# CentralBoard.net
KiCad netlist of a schematic drawn in EAGLE
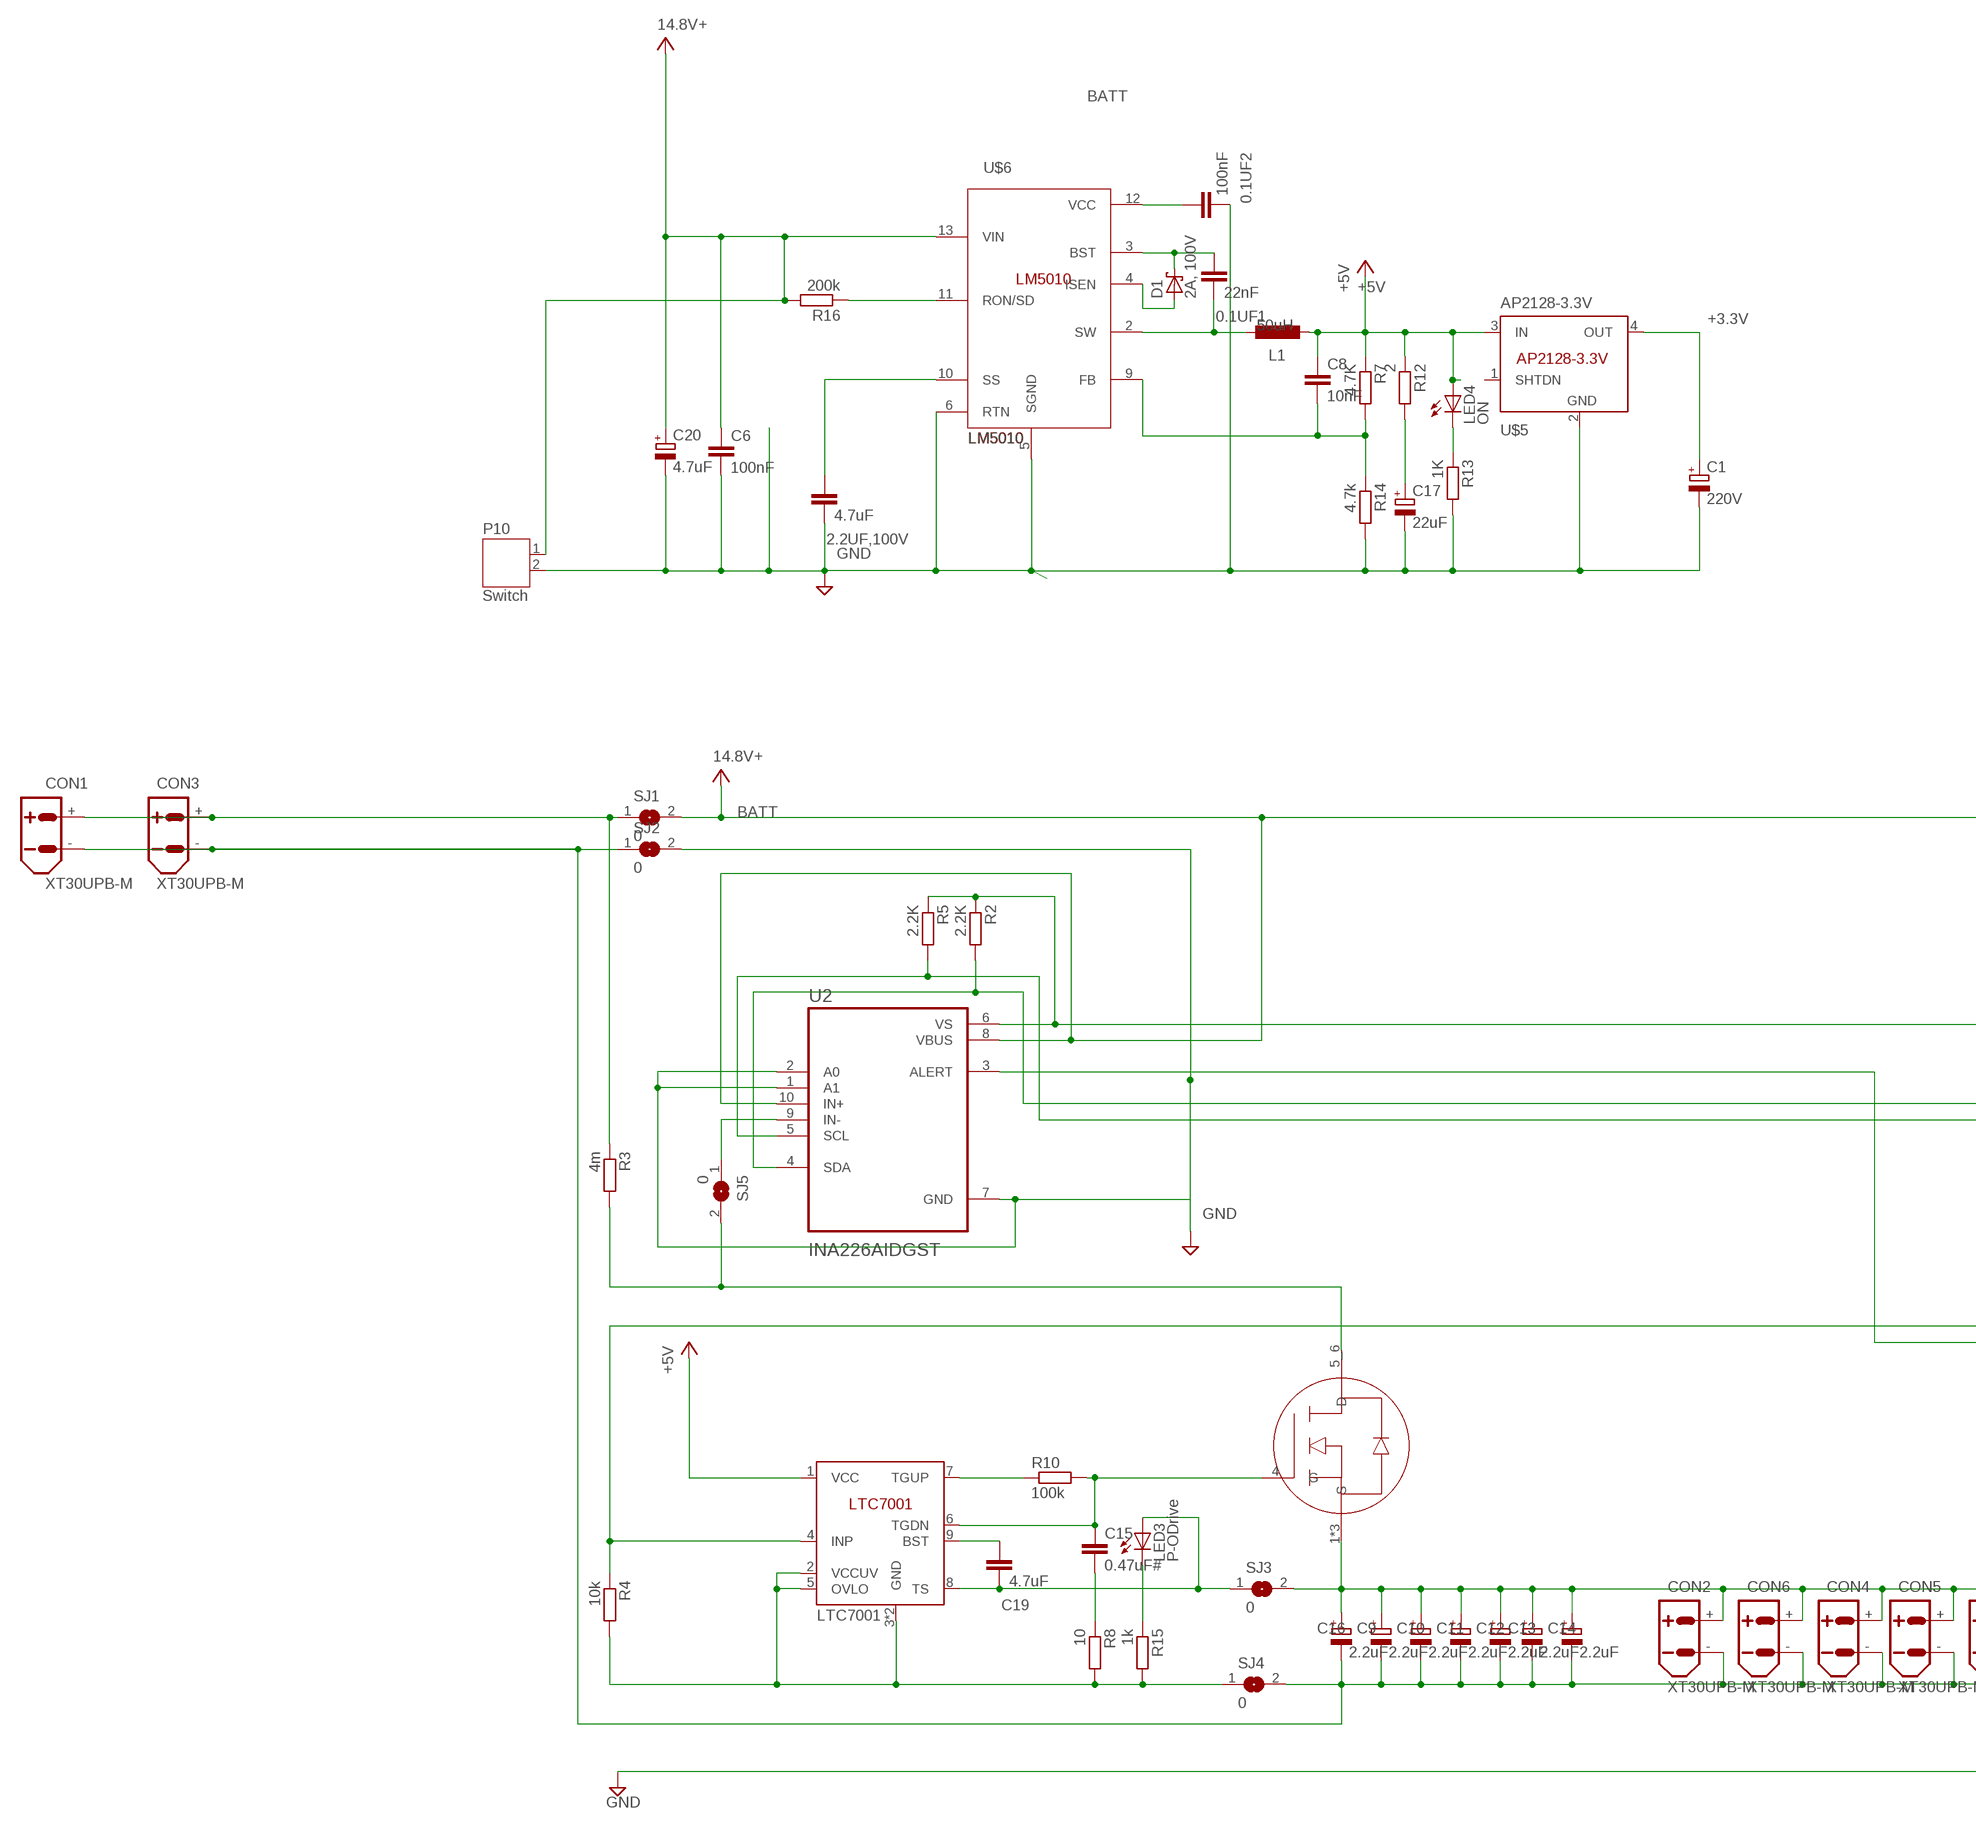
[diagram p0: schematic, sheet 1, part 1 of 2]
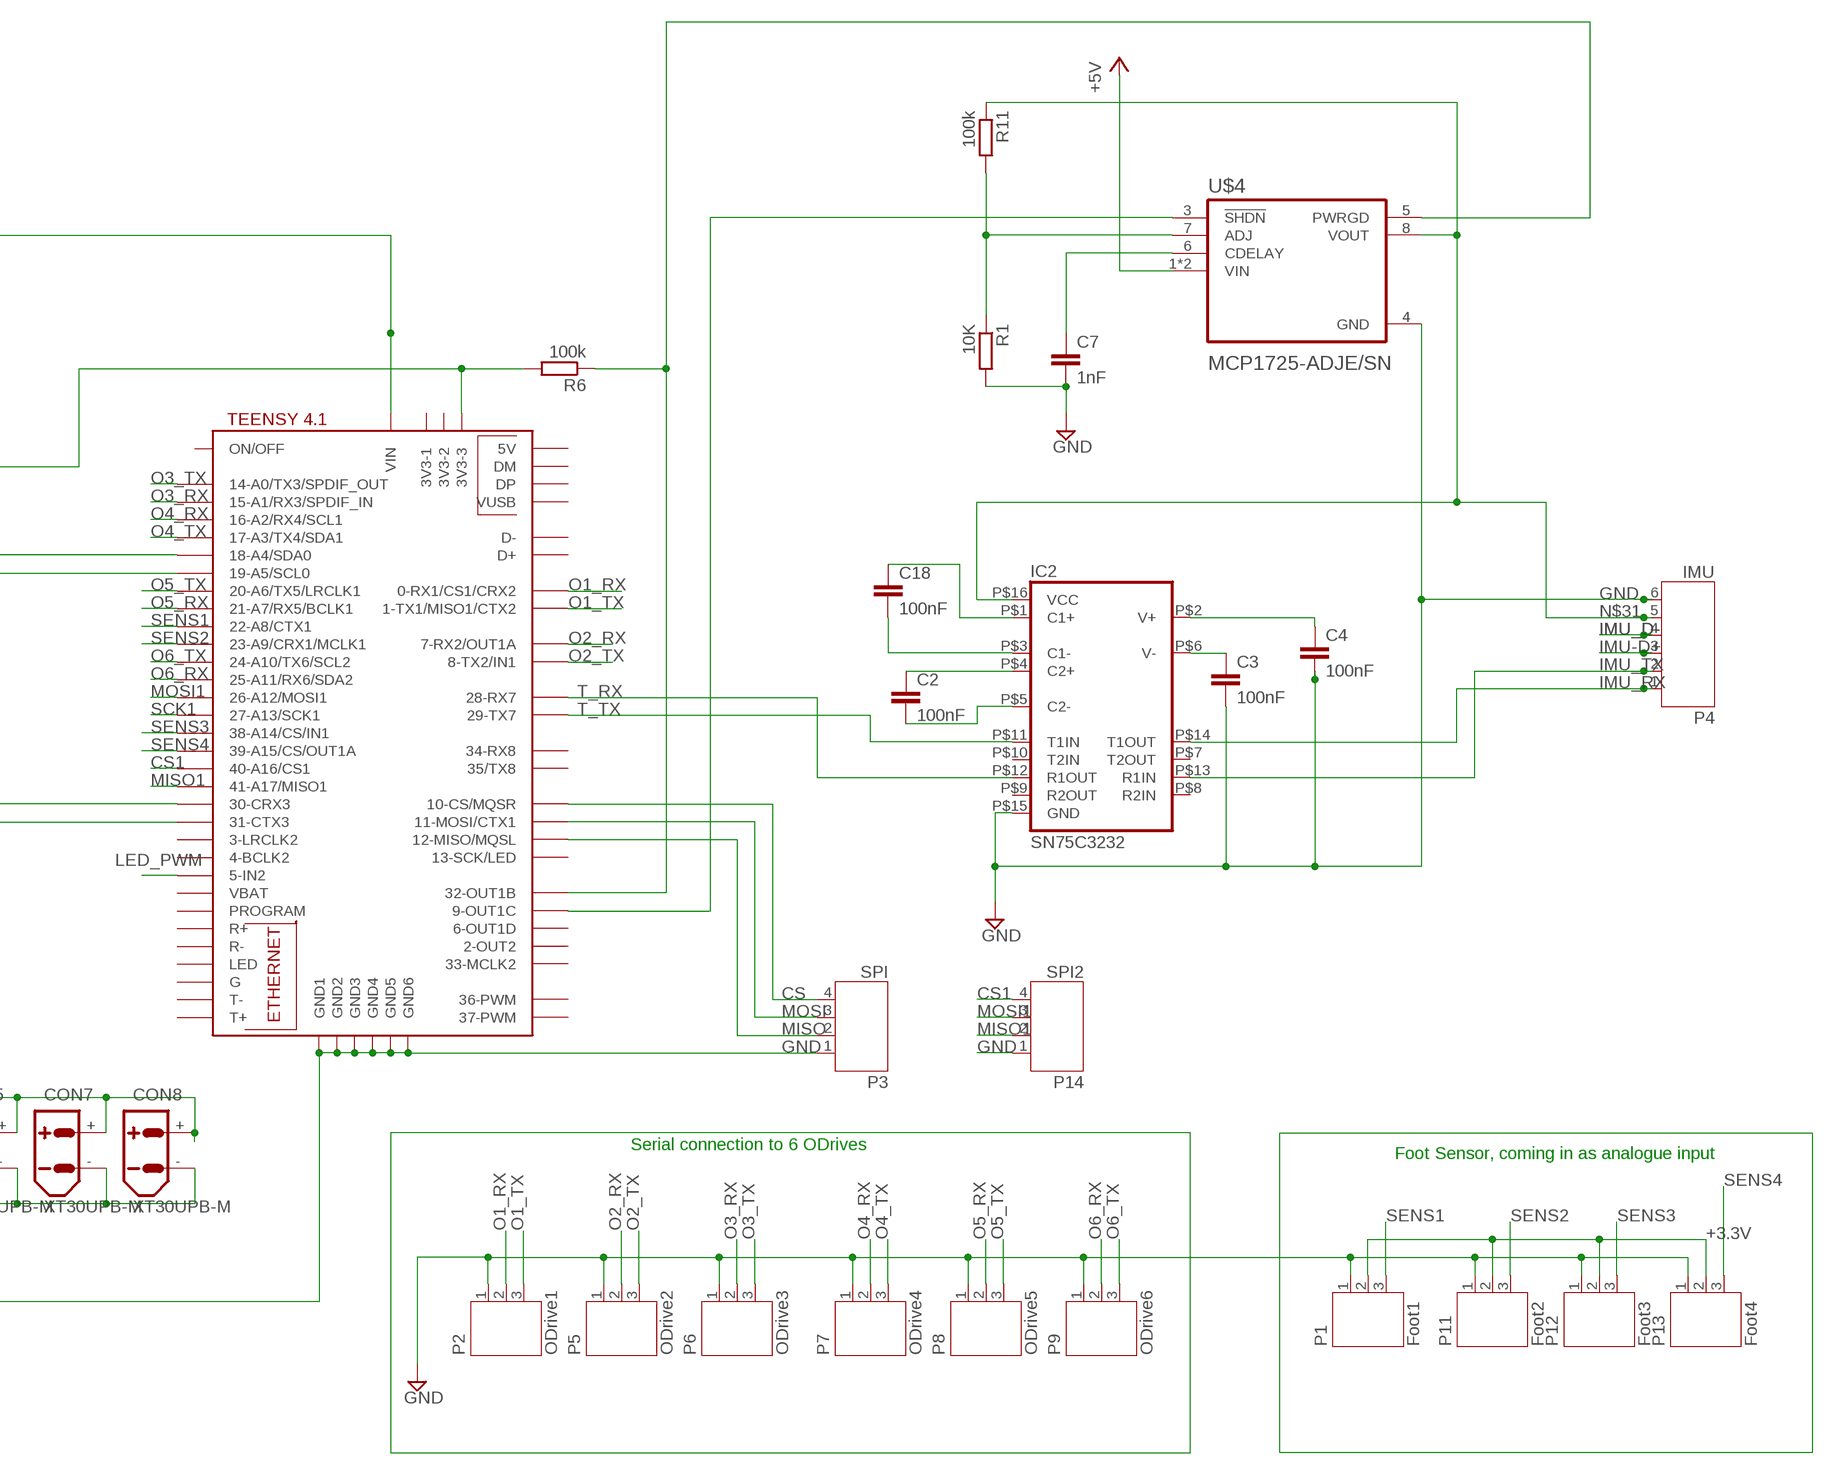
[diagram p1: schematic, sheet 1, part 2 of 2]

(export (version "E")
  (design (tool "Eeschema 10.0.6"))
  (components
    (comp (ref "0.1UF1")
      (value "22nF")
      (footprint "eagle-import:C025-025X050")
      (libsource (lib "eagle-import") (part "C-EU025-025X050"))
    )
    (comp (ref "0.1UF2")
      (value "100nF")
      (footprint "eagle-import:C025-025X050")
      (libsource (lib "eagle-import") (part "C-EU025-025X050"))
    )
    (comp (ref "2.2UF,100V")
      (value "4.7uF")
      (footprint "eagle-import:C025-025X050")
      (libsource (lib "eagle-import") (part "C-EU025-025X050"))
    )
    (comp (ref "C1")
      (value "220V")
      (footprint "eagle-import:E2,5-7")
      (libsource (lib "eagle-import") (part "CPOL-EUE2.5-7"))
    )
    (comp (ref "C2")
      (value "100nF")
      (footprint "eagle-import:C025-025X050")
      (libsource (lib "eagle-import") (part "C-EU025-025X050"))
    )
    (comp (ref "C3")
      (value "100nF")
      (footprint "eagle-import:C025-025X050")
      (libsource (lib "eagle-import") (part "C-EU025-025X050"))
    )
    (comp (ref "C4")
      (value "100nF")
      (footprint "eagle-import:C025-025X050")
      (libsource (lib "eagle-import") (part "C-EU025-025X050"))
    )
    (comp (ref "C6")
      (value "100nF")
      (footprint "eagle-import:C025-025X050")
      (libsource (lib "eagle-import") (part "C-EU025-025X050"))
    )
    (comp (ref "C7")
      (value "1nF")
      (footprint "eagle-import:C025-025X050")
      (libsource (lib "eagle-import") (part "C-EU025-025X050"))
    )
    (comp (ref "C8")
      (value "10nF")
      (footprint "eagle-import:C025-025X050")
      (libsource (lib "eagle-import") (part "C-EU025-025X050"))
    )
    (comp (ref "C9")
      (value "2.2uF")
      (footprint "eagle-import:E2-5")
      (libsource (lib "eagle-import") (part "CPOL-EUE2-5"))
    )
    (comp (ref "C10")
      (value "2.2uF")
      (footprint "eagle-import:E2-5")
      (libsource (lib "eagle-import") (part "CPOL-EUE2-5"))
    )
    (comp (ref "C11")
      (value "2.2uF")
      (footprint "eagle-import:E2-5")
      (libsource (lib "eagle-import") (part "CPOL-EUE2-5"))
    )
    (comp (ref "C12")
      (value "2.2uF")
      (footprint "eagle-import:E2-5")
      (libsource (lib "eagle-import") (part "CPOL-EUE2-5"))
    )
    (comp (ref "C13")
      (value "2.2uF")
      (footprint "eagle-import:E2-5")
      (libsource (lib "eagle-import") (part "CPOL-EUE2-5"))
    )
    (comp (ref "C14")
      (value "2.2uF")
      (footprint "eagle-import:E2-5")
      (libsource (lib "eagle-import") (part "CPOL-EUE2-5"))
    )
    (comp (ref "C15")
      (value "0.47uF#")
      (footprint "eagle-import:C025-025X050")
      (libsource (lib "eagle-import") (part "C-EU025-025X050"))
    )
    (comp (ref "C16")
      (value "2.2uF")
      (footprint "eagle-import:E2-5")
      (libsource (lib "eagle-import") (part "CPOL-EUE2-5"))
    )
    (comp (ref "C17")
      (value "22uF")
      (footprint "eagle-import:E2-4")
      (libsource (lib "eagle-import") (part "CPOL-EUE2-4"))
    )
    (comp (ref "C18")
      (value "100nF")
      (footprint "eagle-import:C025-025X050")
      (libsource (lib "eagle-import") (part "C-EU025-025X050"))
    )
    (comp (ref "C19")
      (value "4.7uF")
      (footprint "eagle-import:C025-025X050")
      (libsource (lib "eagle-import") (part "C-EU025-025X050"))
    )
    (comp (ref "C20")
      (value "4.7uF")
      (footprint "eagle-import:E2-4")
      (libsource (lib "eagle-import") (part "CPOL-EUE2-4"))
    )
    (comp (ref "CON1")
      (value "XT30UPB-M")
      (footprint "eagle-import:XT30UPB-M")
      (libsource (lib "eagle-import") (part "XT30UPB-M"))
    )
    (comp (ref "CON2")
      (value "XT30UPB-M")
      (footprint "eagle-import:XT30UPB-M")
      (libsource (lib "eagle-import") (part "XT30UPB-M"))
    )
    (comp (ref "CON3")
      (value "XT30UPB-M")
      (footprint "eagle-import:XT30UPB-M")
      (libsource (lib "eagle-import") (part "XT30UPB-M"))
    )
    (comp (ref "CON4")
      (value "XT30UPB-M")
      (footprint "eagle-import:XT30UPB-M")
      (libsource (lib "eagle-import") (part "XT30UPB-M"))
    )
    (comp (ref "CON5")
      (value "XT30UPB-M")
      (footprint "eagle-import:XT30UPB-M")
      (libsource (lib "eagle-import") (part "XT30UPB-M"))
    )
    (comp (ref "CON6")
      (value "XT30UPB-M")
      (footprint "eagle-import:XT30UPB-M")
      (libsource (lib "eagle-import") (part "XT30UPB-M"))
    )
    (comp (ref "CON7")
      (value "XT30UPB-M")
      (footprint "eagle-import:XT30UPB-M")
      (libsource (lib "eagle-import") (part "XT30UPB-M"))
    )
    (comp (ref "CON8")
      (value "XT30UPB-M")
      (footprint "eagle-import:XT30UPB-M")
      (libsource (lib "eagle-import") (part "XT30UPB-M"))
    )
    (comp (ref "D1")
      (value "2A, 100V")
      (footprint "eagle-import:DO41-10")
      (libsource (lib "eagle-import") (part "SCHOTTKY-DIODEDO41"))
    )
    (comp (ref "IC2")
      (value "SN75C3232")
      (footprint "eagle-import:SOIC16")
      (fields (field (name "MF") "Maxim Integrated") (field (name "MP") "MAX3232"))
      (libsource (lib "eagle-import") (part "MAX3232"))
    )
    (comp (ref "IC3")
      (value "LTC7001")
      (footprint "eagle-import:MSOP10")
      (fields (field (name "MPN") "AD7992BRMZ-0"))
      (libsource (lib "eagle-import") (part "LTC7001"))
    )
    (comp (ref "L1")
      (value "50uH")
      (footprint "eagle-import:0204_5")
      (libsource (lib "eagle-import") (part "L-EU0204/5"))
    )
    (comp (ref "LED3")
      (value "P-ODrive")
      (footprint "eagle-import:LED3MM")
      (libsource (lib "eagle-import") (part "LED3MM"))
    )
    (comp (ref "LED4")
      (value "ON")
      (footprint "eagle-import:LED3MM")
      (libsource (lib "eagle-import") (part "LED3MM"))
    )
    (comp (ref "P1")
      (value "Foot1")
      (footprint "eagle-import:JST-PH3")
      (libsource (lib "eagle-import") (part "JST-PH3"))
    )
    (comp (ref "P2")
      (value "ODrive1")
      (footprint "eagle-import:JST-PH3")
      (libsource (lib "eagle-import") (part "JST-PH3"))
    )
    (comp (ref "P3")
      (value "SPI")
      (footprint "eagle-import:JST-PH4")
      (libsource (lib "eagle-import") (part "JST-PH4"))
    )
    (comp (ref "P4")
      (value "IMU")
      (footprint "eagle-import:JST-PH6")
      (libsource (lib "eagle-import") (part "JST-PH6"))
    )
    (comp (ref "P5")
      (value "ODrive2")
      (footprint "eagle-import:JST-PH3")
      (libsource (lib "eagle-import") (part "JST-PH3"))
    )
    (comp (ref "P6")
      (value "ODrive3")
      (footprint "eagle-import:JST-PH3")
      (libsource (lib "eagle-import") (part "JST-PH3"))
    )
    (comp (ref "P7")
      (value "ODrive4")
      (footprint "eagle-import:JST-PH3")
      (libsource (lib "eagle-import") (part "JST-PH3"))
    )
    (comp (ref "P8")
      (value "ODrive5")
      (footprint "eagle-import:JST-PH3")
      (libsource (lib "eagle-import") (part "JST-PH3"))
    )
    (comp (ref "P9")
      (value "ODrive6")
      (footprint "eagle-import:JST-PH3")
      (libsource (lib "eagle-import") (part "JST-PH3"))
    )
    (comp (ref "P10")
      (value "Switch")
      (footprint "eagle-import:JST-PH2")
      (libsource (lib "eagle-import") (part "JST-PH2"))
    )
    (comp (ref "P11")
      (value "Foot2")
      (footprint "eagle-import:JST-PH3")
      (libsource (lib "eagle-import") (part "JST-PH3"))
    )
    (comp (ref "P12")
      (value "Foot3")
      (footprint "eagle-import:JST-PH3")
      (libsource (lib "eagle-import") (part "JST-PH3"))
    )
    (comp (ref "P13")
      (value "Foot4")
      (footprint "eagle-import:JST-PH3")
      (libsource (lib "eagle-import") (part "JST-PH3"))
    )
    (comp (ref "P14")
      (value "SPI2")
      (footprint "eagle-import:JST-PH4")
      (libsource (lib "eagle-import") (part "JST-PH4"))
    )
    (comp (ref "R1")
      (value "10K")
      (footprint "eagle-import:0204_7")
      (libsource (lib "eagle-import") (part "R-EU_0204/7"))
    )
    (comp (ref "R2")
      (value "2.2K")
      (footprint "eagle-import:0204_7")
      (libsource (lib "eagle-import") (part "R-EU_0204/7"))
    )
    (comp (ref "R3")
      (value "4m")
      (footprint "eagle-import:R2512")
      (libsource (lib "eagle-import") (part "R-EU_R2512"))
    )
    (comp (ref "R4")
      (value "10k")
      (footprint "eagle-import:0204_7")
      (libsource (lib "eagle-import") (part "R-EU_0204/7"))
    )
    (comp (ref "R5")
      (value "2.2K")
      (footprint "eagle-import:0204_7")
      (libsource (lib "eagle-import") (part "R-EU_0204/7"))
    )
    (comp (ref "R6")
      (value "100k")
      (footprint "eagle-import:0204_7")
      (libsource (lib "eagle-import") (part "R-EU_0204/7"))
    )
    (comp (ref "R7")
      (value "4.7K")
      (footprint "eagle-import:0204_7")
      (libsource (lib "eagle-import") (part "R-EU_0204/7"))
    )
    (comp (ref "R8")
      (value "10")
      (footprint "eagle-import:0204_7")
      (libsource (lib "eagle-import") (part "R-EU_0204/7"))
    )
    (comp (ref "R10")
      (value "100k")
      (footprint "eagle-import:0204_7")
      (libsource (lib "eagle-import") (part "R-EU_0204/7"))
    )
    (comp (ref "R11")
      (value "100k")
      (footprint "eagle-import:0204_7")
      (libsource (lib "eagle-import") (part "R-EU_0204/7"))
    )
    (comp (ref "R12")
      (value "2")
      (footprint "eagle-import:0204_7")
      (libsource (lib "eagle-import") (part "R-EU_0204/7"))
    )
    (comp (ref "R13")
      (value "1K")
      (footprint "eagle-import:0204_7")
      (libsource (lib "eagle-import") (part "R-EU_0204/7"))
    )
    (comp (ref "R14")
      (value "4.7k")
      (footprint "eagle-import:0204_7")
      (libsource (lib "eagle-import") (part "R-EU_0204/7"))
    )
    (comp (ref "R15")
      (value "1k")
      (footprint "eagle-import:0204_7")
      (libsource (lib "eagle-import") (part "R-EU_0204/7"))
    )
    (comp (ref "R16")
      (value "200k")
      (footprint "eagle-import:0204_7")
      (libsource (lib "eagle-import") (part "R-EU_0204/7"))
    )
    (comp (ref "SJ1") (value "0") (footprint "eagle-import:SJ") (libsource (lib "eagle-import") (part "SJ")))
    (comp (ref "SJ2") (value "0") (footprint "eagle-import:SJ") (libsource (lib "eagle-import") (part "SJ")))
    (comp (ref "SJ3") (value "0") (footprint "eagle-import:SJ") (libsource (lib "eagle-import") (part "SJ")))
    (comp (ref "SJ4") (value "0") (footprint "eagle-import:SJ") (libsource (lib "eagle-import") (part "SJ")))
    (comp (ref "SJ5") (value "0") (footprint "eagle-import:SJ") (libsource (lib "eagle-import") (part "SJ")))
    (comp (ref "U$1")
      (value "TEENSY41")
      (footprint "eagle-import:TEENSY41")
      (libsource (lib "eagle-import") (part "TEENSY41"))
    )
    (comp (ref "U$2")
      (value "DMTH8003SPS")
      (footprint "eagle-import:DIO_NTS1045EMFST1G")
      (libsource (lib "eagle-import") (part "NVMFS6H824NL-D"))
    )
    (comp (ref "U$4")
      (value "MCP1725-ADJE/SN")
      (footprint "eagle-import:SOIC127P599X175-8N")
      (fields (field (name "MF") "Microchip"))
      (libsource (lib "eagle-import") (part "MCP1725-ADJE/SN"))
    )
    (comp (ref "U$5")
      (value "AP2128-3.3V")
      (footprint "eagle-import:SOT-23-5")
      (libsource (lib "eagle-import") (part "AP2128-3.3V"))
    )
    (comp (ref "U$6")
      (value "LM5010")
      (footprint "eagle-import:TSSOP-14")
      (libsource (lib "eagle-import") (part "LM5010"))
    )
    (comp (ref "U2")
      (value "INA226AIDGST")
      (footprint "eagle-import:SOP50P490X110-10N")
      (fields (field (name "MF") "Texas Instruments"))
      (libsource (lib "eagle-import") (part "INA226AIDGST"))
    )
  )
  (nets
    (net (code "1") (name "+5V") (class "Default")
      (node (ref "C8") (pin "1") (pinfunction "1_1") (pintype "passive"))
      (node (ref "IC3") (pin "1") (pinfunction "VCC_1") (pintype "power_in"))
      (node (ref "L1") (pin "2") (pinfunction "2_2") (pintype "passive"))
      (node (ref "LED4") (pin "A") (pinfunction "A_A") (pintype "passive"))
      (node (ref "R12") (pin "1") (pinfunction "1_1") (pintype "passive"))
      (node (ref "R7") (pin "1") (pinfunction "1_1") (pintype "passive"))
      (node (ref "U$4") (pin "1") (pinfunction "VIN_1") (pintype "input"))
      (node (ref "U$4") (pin "2") (pinfunction "VIN_2") (pintype "input"))
      (node (ref "U$5") (pin "3") (pinfunction "IN_3") (pintype "input"))
    )
    (net (code "2") (name "/+3.3V") (class "Default")
      (node (ref "C1") (pin "+") (pinfunction "+_+") (pintype "passive"))
      (node (ref "P1") (pin "2") (pinfunction "2_2") (pintype "passive"))
      (node (ref "P11") (pin "2") (pinfunction "2_2") (pintype "passive"))
      (node (ref "P12") (pin "2") (pinfunction "2_2") (pintype "passive"))
      (node (ref "P13") (pin "2") (pinfunction "2_2") (pintype "passive"))
      (node (ref "U$5") (pin "4") (pinfunction "OUT_4") (pintype "output"))
    )
    (net (code "3") (name "/CS") (class "Default")
      (node (ref "P3") (pin "4") (pinfunction "4_4") (pintype "passive"))
      (node (ref "U$1") (pin "10-CS\\MQSR") (pinfunction "10-CS/MQSR_10-CS\\MQSR") (pintype "bidirectional"))
    )
    (net (code "4") (name "/CS1") (class "Default")
      (node (ref "P14") (pin "4") (pinfunction "4_4") (pintype "passive"))
      (node (ref "U$1") (pin "40-A16/CS1") (pinfunction "40-A16/CS1_40-A16/CS1") (pintype "bidirectional"))
    )
    (net (code "5") (name "/IMU-D+") (class "Default")
      (node (ref "P4") (pin "3") (pinfunction "3_3") (pintype "passive"))
    )
    (net (code "6") (name "/IMU_D-") (class "Default")
      (node (ref "P4") (pin "4") (pinfunction "4_4") (pintype "passive"))
    )
    (net (code "7") (name "/IMU_RX") (class "Default")
      (node (ref "IC2") (pin "P$14") (pinfunction "T1OUT_P$14") (pintype "output"))
      (node (ref "P4") (pin "1") (pinfunction "1_1") (pintype "passive"))
    )
    (net (code "8") (name "/IMU_TX") (class "Default")
      (node (ref "IC2") (pin "P$13") (pinfunction "R1IN_P$13") (pintype "input"))
      (node (ref "P4") (pin "2") (pinfunction "2_2") (pintype "passive"))
    )
    (net (code "9") (name "/LED_PWM") (class "Default")
      (node (ref "U$1") (pin "5-IN2") (pinfunction "5-IN2_5-IN2") (pintype "bidirectional"))
    )
    (net (code "10") (name "/MISO") (class "Default")
      (node (ref "P3") (pin "2") (pinfunction "2_2") (pintype "passive"))
      (node (ref "U$1") (pin "12-MISO/MQSL") (pinfunction "12-MISO/MQSL_12-MISO/MQSL") (pintype "bidirectional"))
    )
    (net (code "11") (name "/MISO1") (class "Default")
      (node (ref "P14") (pin "2") (pinfunction "2_2") (pintype "passive"))
      (node (ref "U$1") (pin "41-A17/MISO1") (pinfunction "41-A17/MISO1_41-A17/MISO1") (pintype "bidirectional"))
    )
    (net (code "12") (name "/MOSI") (class "Default")
      (node (ref "P3") (pin "3") (pinfunction "3_3") (pintype "passive"))
      (node (ref "U$1") (pin "11-MOSI/CTX1") (pinfunction "11-MOSI/CTX1_11-MOSI/CTX1") (pintype "bidirectional"))
    )
    (net (code "13") (name "/MOSI1") (class "Default")
      (node (ref "P14") (pin "3") (pinfunction "3_3") (pintype "passive"))
      (node (ref "U$1") (pin "26-A12/MOSI1") (pinfunction "26-A12/MOSI1_26-A12/MOSI1") (pintype "bidirectional"))
    )
    (net (code "14") (name "/N$31") (class "Default")
      (node (ref "IC2") (pin "P$16") (pinfunction "VCC_P$16") (pintype "power_in"))
      (node (ref "P4") (pin "5") (pinfunction "5_5") (pintype "passive"))
      (node (ref "R11") (pin "1") (pinfunction "1_1") (pintype "passive"))
      (node (ref "U$4") (pin "8") (pinfunction "VOUT_8") (pintype "output"))
    )
    (net (code "15") (name "/O1_RX") (class "Default")
      (node (ref "P2") (pin "2") (pinfunction "2_2") (pintype "passive"))
      (node (ref "U$1") (pin "0-RX1/CS1/CRX2") (pinfunction "0-RX1/CS1/CRX2_0-RX1/CS1/CRX2") (pintype "bidirectional"))
    )
    (net (code "16") (name "/O1_TX") (class "Default")
      (node (ref "P2") (pin "3") (pinfunction "3_3") (pintype "passive"))
      (node (ref "U$1") (pin "1-TX1/MISO1/CTX2") (pinfunction "1-TX1/MISO1/CTX2_1-TX1/MISO1/CTX2") (pintype "bidirectional"))
    )
    (net (code "17") (name "/O2_RX") (class "Default")
      (node (ref "P5") (pin "2") (pinfunction "2_2") (pintype "passive"))
      (node (ref "U$1") (pin "7-RX2/OUT1A") (pinfunction "7-RX2/OUT1A_7-RX2/OUT1A") (pintype "bidirectional"))
    )
    (net (code "18") (name "/O2_TX") (class "Default")
      (node (ref "P5") (pin "3") (pinfunction "3_3") (pintype "passive"))
      (node (ref "U$1") (pin "8-TX2/IN1") (pinfunction "8-TX2/IN1_8-TX2/IN1") (pintype "bidirectional"))
    )
    (net (code "19") (name "/O3_RX") (class "Default")
      (node (ref "P6") (pin "2") (pinfunction "2_2") (pintype "passive"))
      (node (ref "U$1") (pin "15-A1/RX3/SPDIF_IN") (pinfunction "15-A1/RX3/SPDIF_IN_15-A1/RX3/SPDIF_IN") (pintype "bidirectional"))
    )
    (net (code "20") (name "/O3_TX") (class "Default")
      (node (ref "P6") (pin "3") (pinfunction "3_3") (pintype "passive"))
      (node (ref "U$1") (pin "14-A0/TX3/SPDIF_OUT") (pinfunction "14-A0/TX3/SPDIF_OUT_14-A0/TX3/SPDIF_OUT") (pintype "bidirectional"))
    )
    (net (code "21") (name "/O4_RX") (class "Default")
      (node (ref "P7") (pin "2") (pinfunction "2_2") (pintype "passive"))
      (node (ref "U$1") (pin "16-A2/RX4/SCL1") (pinfunction "16-A2/RX4/SCL1_16-A2/RX4/SCL1") (pintype "bidirectional"))
    )
    (net (code "22") (name "/O4_TX") (class "Default")
      (node (ref "P7") (pin "3") (pinfunction "3_3") (pintype "passive"))
      (node (ref "U$1") (pin "17-A3/TX4/SDA1") (pinfunction "17-A3/TX4/SDA1_17-A3/TX4/SDA1") (pintype "bidirectional"))
    )
    (net (code "23") (name "/O5_RX") (class "Default")
      (node (ref "P8") (pin "2") (pinfunction "2_2") (pintype "passive"))
      (node (ref "U$1") (pin "21-A7/RX5/BCLK1") (pinfunction "21-A7/RX5/BCLK1_21-A7/RX5/BCLK1") (pintype "bidirectional"))
    )
    (net (code "24") (name "/O5_TX") (class "Default")
      (node (ref "P8") (pin "3") (pinfunction "3_3") (pintype "passive"))
      (node (ref "U$1") (pin "20-A6/TX5/LRCLK1") (pinfunction "20-A6/TX5/LRCLK1_20-A6/TX5/LRCLK1") (pintype "bidirectional"))
    )
    (net (code "25") (name "/O6_RX") (class "Default")
      (node (ref "P9") (pin "2") (pinfunction "2_2") (pintype "passive"))
      (node (ref "U$1") (pin "25-A11/RX6/SDA2") (pinfunction "25-A11/RX6/SDA2_25-A11/RX6/SDA2") (pintype "bidirectional"))
    )
    (net (code "26") (name "/O6_TX") (class "Default")
      (node (ref "P9") (pin "3") (pinfunction "3_3") (pintype "passive"))
      (node (ref "U$1") (pin "24-A10/TX6/SCL2") (pinfunction "24-A10/TX6/SCL2_24-A10/TX6/SCL2") (pintype "bidirectional"))
    )
    (net (code "27") (name "/SCK1") (class "Default")
      (node (ref "U$1") (pin "27-A13/SCK1") (pinfunction "27-A13/SCK1_27-A13/SCK1") (pintype "bidirectional"))
    )
    (net (code "28") (name "/SENS1") (class "Default")
      (node (ref "P1") (pin "3") (pinfunction "3_3") (pintype "passive"))
      (node (ref "U$1") (pin "22-A8/CTX1") (pinfunction "22-A8/CTX1_22-A8/CTX1") (pintype "bidirectional"))
    )
    (net (code "29") (name "/SENS2") (class "Default")
      (node (ref "P11") (pin "3") (pinfunction "3_3") (pintype "passive"))
      (node (ref "U$1") (pin "23-A9/CRX1/MCLK1") (pinfunction "23-A9/CRX1/MCLK1_23-A9/CRX1/MCLK1") (pintype "bidirectional"))
    )
    (net (code "30") (name "/SENS3") (class "Default")
      (node (ref "P12") (pin "3") (pinfunction "3_3") (pintype "passive"))
      (node (ref "U$1") (pin "38-A14/CS/IN1") (pinfunction "38-A14/CS/IN1_38-A14/CS/IN1") (pintype "bidirectional"))
    )
    (net (code "31") (name "/SENS4") (class "Default")
      (node (ref "P13") (pin "3") (pinfunction "3_3") (pintype "passive"))
      (node (ref "U$1") (pin "39-A15/CS/OUT1A") (pinfunction "39-A15/CS/OUT1A_39-A15/CS/OUT1A") (pintype "bidirectional"))
    )
    (net (code "32") (name "/T_RX") (class "Default")
      (node (ref "IC2") (pin "P$12") (pinfunction "R1OUT_P$12") (pintype "output"))
      (node (ref "U$1") (pin "28-RX7") (pinfunction "28-RX7_28-RX7") (pintype "bidirectional"))
    )
    (net (code "33") (name "/T_TX") (class "Default")
      (node (ref "IC2") (pin "P$11") (pinfunction "T1IN_P$11") (pintype "input"))
      (node (ref "U$1") (pin "29-TX7") (pinfunction "29-TX7_29-TX7") (pintype "bidirectional"))
    )
    (net (code "34") (name "14.8V+") (class "Default")
      (node (ref "C20") (pin "+") (pinfunction "+_+") (pintype "passive"))
      (node (ref "C6") (pin "1") (pinfunction "1_1") (pintype "passive"))
      (node (ref "P10") (pin "1") (pinfunction "1_1") (pintype "passive"))
      (node (ref "R16") (pin "2") (pinfunction "2_2") (pintype "passive"))
      (node (ref "SJ1") (pin "2") (pinfunction "2_2") (pintype "passive"))
      (node (ref "U$6") (pin "13") (pinfunction "VIN_13") (pintype "bidirectional"))
      (node (ref "U2") (pin "10") (pinfunction "IN+_10") (pintype "input"))
      (node (ref "U2") (pin "8") (pinfunction "VBUS_8") (pintype "power_in"))
    )
    (net (code "35") (name "GND") (class "Default")
      (node (ref "0.1UF2") (pin "2") (pinfunction "2_2") (pintype "passive"))
      (node (ref "2.2UF,100V") (pin "2") (pinfunction "2_2") (pintype "passive"))
      (node (ref "C1") (pin "-") (pinfunction "-_-") (pintype "passive"))
      (node (ref "C17") (pin "-") (pinfunction "-_-") (pintype "passive"))
      (node (ref "C20") (pin "-") (pinfunction "-_-") (pintype "passive"))
      (node (ref "C3") (pin "2") (pinfunction "2_2") (pintype "passive"))
      (node (ref "C4") (pin "2") (pinfunction "2_2") (pintype "passive"))
      (node (ref "C6") (pin "2") (pinfunction "2_2") (pintype "passive"))
      (node (ref "C7") (pin "2") (pinfunction "2_2") (pintype "passive"))
      (node (ref "IC2") (pin "P$15") (pinfunction "GND_P$15") (pintype "power_in"))
      (node (ref "P1") (pin "1") (pinfunction "1_1") (pintype "passive"))
      (node (ref "P10") (pin "2") (pinfunction "2_2") (pintype "passive"))
      (node (ref "P11") (pin "1") (pinfunction "1_1") (pintype "passive"))
      (node (ref "P12") (pin "1") (pinfunction "1_1") (pintype "passive"))
      (node (ref "P13") (pin "1") (pinfunction "1_1") (pintype "passive"))
      (node (ref "P14") (pin "1") (pinfunction "1_1") (pintype "passive"))
      (node (ref "P2") (pin "1") (pinfunction "1_1") (pintype "passive"))
      (node (ref "P3") (pin "1") (pinfunction "1_1") (pintype "passive"))
      (node (ref "P4") (pin "6") (pinfunction "6_6") (pintype "passive"))
      (node (ref "P5") (pin "1") (pinfunction "1_1") (pintype "passive"))
      (node (ref "P6") (pin "1") (pinfunction "1_1") (pintype "passive"))
      (node (ref "P7") (pin "1") (pinfunction "1_1") (pintype "passive"))
      (node (ref "P8") (pin "1") (pinfunction "1_1") (pintype "passive"))
      (node (ref "P9") (pin "1") (pinfunction "1_1") (pintype "passive"))
      (node (ref "R1") (pin "2") (pinfunction "2_2") (pintype "passive"))
      (node (ref "R13") (pin "2") (pinfunction "2_2") (pintype "passive"))
      (node (ref "R14") (pin "2") (pinfunction "2_2") (pintype "passive"))
      (node (ref "SJ2") (pin "2") (pinfunction "2_2") (pintype "passive"))
      (node (ref "U$1") (pin "GND1") (pinfunction "GND1_GND1") (pintype "bidirectional"))
      (node (ref "U$1") (pin "GND2") (pinfunction "GND2_GND2") (pintype "bidirectional"))
      (node (ref "U$1") (pin "GND3") (pinfunction "GND3_GND3") (pintype "bidirectional"))
      (node (ref "U$1") (pin "GND4") (pinfunction "GND4_GND4") (pintype "bidirectional"))
      (node (ref "U$1") (pin "GND5") (pinfunction "GND5_GND5") (pintype "bidirectional"))
      (node (ref "U$1") (pin "GND6") (pinfunction "GND6_GND6") (pintype "bidirectional"))
      (node (ref "U$4") (pin "4") (pinfunction "GND_4") (pintype "power_in"))
      (node (ref "U$5") (pin "2") (pinfunction "GND_2") (pintype "power_in"))
      (node (ref "U$6") (pin "5") (pinfunction "SGND_5") (pintype "bidirectional"))
      (node (ref "U$6") (pin "6") (pinfunction "RTN_6") (pintype "bidirectional"))
      (node (ref "U2") (pin "1") (pinfunction "A1_1") (pintype "input"))
      (node (ref "U2") (pin "2") (pinfunction "A0_2") (pintype "input"))
      (node (ref "U2") (pin "7") (pinfunction "GND_7") (pintype "power_in"))
    )
    (net (code "36") (name "Net-(C10-Pad+)") (class "Default")
      (node (ref "C10") (pin "+") (pinfunction "+_+") (pintype "passive"))
      (node (ref "C11") (pin "+") (pinfunction "+_+") (pintype "passive"))
      (node (ref "C12") (pin "+") (pinfunction "+_+") (pintype "passive"))
      (node (ref "C13") (pin "+") (pinfunction "+_+") (pintype "passive"))
      (node (ref "C14") (pin "+") (pinfunction "+_+") (pintype "passive"))
      (node (ref "C16") (pin "+") (pinfunction "+_+") (pintype "passive"))
      (node (ref "C9") (pin "+") (pinfunction "+_+") (pintype "passive"))
      (node (ref "CON2") (pin "+") (pinfunction "+_+") (pintype "power_in"))
      (node (ref "CON4") (pin "+") (pinfunction "+_+") (pintype "power_in"))
      (node (ref "CON5") (pin "+") (pinfunction "+_+") (pintype "power_in"))
      (node (ref "CON6") (pin "+") (pinfunction "+_+") (pintype "power_in"))
      (node (ref "CON7") (pin "+") (pinfunction "+_+") (pintype "power_in"))
      (node (ref "CON8") (pin "+") (pinfunction "+_+") (pintype "power_in"))
      (node (ref "SJ3") (pin "2") (pinfunction "2_2") (pintype "passive"))
      (node (ref "U$2") (pin "1") (pinfunction "S_1") (pintype "bidirectional"))
      (node (ref "U$2") (pin "2") (pinfunction "S_2") (pintype "bidirectional"))
      (node (ref "U$2") (pin "3") (pinfunction "S_3") (pintype "bidirectional"))
    )
    (net (code "37") (name "Net-(C10-Pad-)") (class "Default")
      (node (ref "C10") (pin "-") (pinfunction "-_-") (pintype "passive"))
      (node (ref "C11") (pin "-") (pinfunction "-_-") (pintype "passive"))
      (node (ref "C12") (pin "-") (pinfunction "-_-") (pintype "passive"))
      (node (ref "C13") (pin "-") (pinfunction "-_-") (pintype "passive"))
      (node (ref "C14") (pin "-") (pinfunction "-_-") (pintype "passive"))
      (node (ref "C16") (pin "-") (pinfunction "-_-") (pintype "passive"))
      (node (ref "C9") (pin "-") (pinfunction "-_-") (pintype "passive"))
      (node (ref "CON1") (pin "-") (pinfunction "-_-") (pintype "power_in"))
      (node (ref "CON2") (pin "-") (pinfunction "-_-") (pintype "power_in"))
      (node (ref "CON3") (pin "-") (pinfunction "-_-") (pintype "power_in"))
      (node (ref "CON4") (pin "-") (pinfunction "-_-") (pintype "power_in"))
      (node (ref "CON5") (pin "-") (pinfunction "-_-") (pintype "power_in"))
      (node (ref "CON6") (pin "-") (pinfunction "-_-") (pintype "power_in"))
      (node (ref "CON7") (pin "-") (pinfunction "-_-") (pintype "power_in"))
      (node (ref "CON8") (pin "-") (pinfunction "-_-") (pintype "power_in"))
      (node (ref "SJ2") (pin "1") (pinfunction "1_1") (pintype "passive"))
      (node (ref "SJ4") (pin "2") (pinfunction "2_2") (pintype "passive"))
    )
    (net (code "38") (name "Net-(C15-Pad2)") (class "Default")
      (node (ref "C15") (pin "2") (pinfunction "2_2") (pintype "passive"))
      (node (ref "R8") (pin "1") (pinfunction "1_1") (pintype "passive"))
    )
    (net (code "39") (name "Net-(C17-Pad+)") (class "Default")
      (node (ref "C17") (pin "+") (pinfunction "+_+") (pintype "passive"))
      (node (ref "R12") (pin "2") (pinfunction "2_2") (pintype "passive"))
    )
    (net (code "40") (name "Net-(CON1-Pad+)") (class "Default")
      (node (ref "CON1") (pin "+") (pinfunction "+_+") (pintype "power_in"))
      (node (ref "CON3") (pin "+") (pinfunction "+_+") (pintype "power_in"))
      (node (ref "R3") (pin "1") (pinfunction "1_1") (pintype "passive"))
      (node (ref "SJ1") (pin "1") (pinfunction "1_1") (pintype "passive"))
    )
    (net (code "41") (name "Net-(IC2-C1+)") (class "Default")
      (node (ref "C18") (pin "1") (pinfunction "1_1") (pintype "passive"))
      (node (ref "IC2") (pin "P$1") (pinfunction "C1+_P$1") (pintype "passive"))
    )
    (net (code "42") (name "Net-(IC2-C1-)") (class "Default")
      (node (ref "C18") (pin "2") (pinfunction "2_2") (pintype "passive"))
      (node (ref "IC2") (pin "P$3") (pinfunction "C1-_P$3") (pintype "passive"))
    )
    (net (code "43") (name "Net-(IC2-C2+)") (class "Default")
      (node (ref "C2") (pin "1") (pinfunction "1_1") (pintype "passive"))
      (node (ref "IC2") (pin "P$4") (pinfunction "C2+_P$4") (pintype "passive"))
    )
    (net (code "44") (name "Net-(IC2-C2-)") (class "Default")
      (node (ref "C2") (pin "2") (pinfunction "2_2") (pintype "passive"))
      (node (ref "IC2") (pin "P$5") (pinfunction "C2-_P$5") (pintype "passive"))
    )
    (net (code "45") (name "Net-(IC2-V+)") (class "Default")
      (node (ref "C4") (pin "1") (pinfunction "1_1") (pintype "passive"))
      (node (ref "IC2") (pin "P$2") (pinfunction "V+_P$2") (pintype "passive"))
    )
    (net (code "46") (name "Net-(IC2-V-)") (class "Default")
      (node (ref "C3") (pin "1") (pinfunction "1_1") (pintype "passive"))
      (node (ref "IC2") (pin "P$6") (pinfunction "V-_P$6") (pintype "passive"))
    )
    (net (code "47") (name "Net-(IC3-BST)") (class "Default")
      (node (ref "C19") (pin "1") (pinfunction "1_1") (pintype "passive"))
      (node (ref "IC3") (pin "9") (pinfunction "BST_9") (pintype "input"))
    )
    (net (code "48") (name "Net-(IC3-INP)") (class "Default")
      (node (ref "IC3") (pin "4") (pinfunction "INP_4") (pintype "input"))
      (node (ref "R4") (pin "1") (pinfunction "1_1") (pintype "passive"))
      (node (ref "U$1") (pin "30-CRX3") (pinfunction "30-CRX3_30-CRX3") (pintype "bidirectional"))
    )
    (net (code "49") (name "Net-(IC3-OVLO)") (class "Default")
      (node (ref "IC3") (pin "11") (pinfunction "GND_11") (pintype "power_in"))
      (node (ref "IC3") (pin "2") (pinfunction "VCCUV_2") (pintype "input"))
      (node (ref "IC3") (pin "3") (pinfunction "GND_3") (pintype "power_in"))
      (node (ref "IC3") (pin "5") (pinfunction "OVLO_5") (pintype "power_in"))
      (node (ref "R15") (pin "2") (pinfunction "2_2") (pintype "passive"))
      (node (ref "R4") (pin "2") (pinfunction "2_2") (pintype "passive"))
      (node (ref "R8") (pin "2") (pinfunction "2_2") (pintype "passive"))
      (node (ref "SJ4") (pin "1") (pinfunction "1_1") (pintype "passive"))
    )
    (net (code "50") (name "Net-(IC3-TGDN)") (class "Default")
      (node (ref "C15") (pin "1") (pinfunction "1_1") (pintype "passive"))
      (node (ref "IC3") (pin "6") (pinfunction "TGDN_6") (pintype "output"))
      (node (ref "R10") (pin "2") (pinfunction "2_2") (pintype "passive"))
      (node (ref "U$2") (pin "4") (pinfunction "G_4") (pintype "bidirectional"))
    )
    (net (code "51") (name "Net-(IC3-TGUP)") (class "Default")
      (node (ref "IC3") (pin "7") (pinfunction "TGUP_7") (pintype "input"))
      (node (ref "R10") (pin "1") (pinfunction "1_1") (pintype "passive"))
    )
    (net (code "52") (name "Net-(IC3-TS)") (class "Default")
      (node (ref "C19") (pin "2") (pinfunction "2_2") (pintype "passive"))
      (node (ref "IC3") (pin "8") (pinfunction "TS_8") (pintype "bidirectional"))
      (node (ref "LED3") (pin "A") (pinfunction "A_A") (pintype "passive"))
      (node (ref "SJ3") (pin "1") (pinfunction "1_1") (pintype "passive"))
    )
    (net (code "53") (name "Net-(LED3-C)") (class "Default")
      (node (ref "LED3") (pin "K") (pinfunction "C_K") (pintype "passive"))
      (node (ref "R15") (pin "1") (pinfunction "1_1") (pintype "passive"))
    )
    (net (code "54") (name "Net-(LED4-C)") (class "Default")
      (node (ref "LED4") (pin "K") (pinfunction "C_K") (pintype "passive"))
      (node (ref "R13") (pin "1") (pinfunction "1_1") (pintype "passive"))
    )
    (net (code "55") (name "Net-(U$2-D)") (class "Default")
      (node (ref "R3") (pin "2") (pinfunction "2_2") (pintype "passive"))
      (node (ref "SJ5") (pin "2") (pinfunction "2_2") (pintype "passive"))
      (node (ref "U$2") (pin "5_6") (pinfunction "D_5_6") (pintype "bidirectional"))
    )
    (net (code "56") (name "Net-(U$4-ADJ)") (class "Default")
      (node (ref "R1") (pin "1") (pinfunction "1_1") (pintype "passive"))
      (node (ref "R11") (pin "2") (pinfunction "2_2") (pintype "passive"))
      (node (ref "U$4") (pin "7") (pinfunction "ADJ_7") (pintype "input"))
    )
    (net (code "57") (name "Net-(U$4-CDELAY)") (class "Default")
      (node (ref "C7") (pin "1") (pinfunction "1_1") (pintype "passive"))
      (node (ref "U$4") (pin "6") (pinfunction "CDELAY_6") (pintype "input"))
    )
    (net (code "58") (name "Net-(U$4-PWRGD)") (class "Default")
      (node (ref "R6") (pin "1") (pinfunction "1_1") (pintype "passive"))
      (node (ref "U$1") (pin "32-OUT1B") (pinfunction "32-OUT1B_32-OUT1B") (pintype "bidirectional"))
      (node (ref "U$4") (pin "5") (pinfunction "PWRGD_5") (pintype "output"))
    )
    (net (code "59") (name "Net-(U$4-~{SHDN})") (class "Default")
      (node (ref "U$1") (pin "9-OUT1C") (pinfunction "9-OUT1C_9-OUT1C") (pintype "bidirectional"))
      (node (ref "U$4") (pin "3") (pinfunction "~{SHDN}_3") (pintype "input"))
    )
    (net (code "60") (name "Net-(U$6-BST)") (class "Default")
      (node (ref "0.1UF1") (pin "1") (pinfunction "1_1") (pintype "passive"))
      (node (ref "D1") (pin "C") (pinfunction "C_C") (pintype "passive"))
      (node (ref "U$6") (pin "3") (pinfunction "BST_3") (pintype "bidirectional"))
    )
    (net (code "61") (name "Net-(U$6-FB)") (class "Default")
      (node (ref "C8") (pin "2") (pinfunction "2_2") (pintype "passive"))
      (node (ref "R14") (pin "1") (pinfunction "1_1") (pintype "passive"))
      (node (ref "R7") (pin "2") (pinfunction "2_2") (pintype "passive"))
      (node (ref "U$6") (pin "9") (pinfunction "FB_9") (pintype "bidirectional"))
    )
    (net (code "62") (name "Net-(U$6-ISEN)") (class "Default")
      (node (ref "D1") (pin "A") (pinfunction "A_A") (pintype "passive"))
      (node (ref "U$6") (pin "4") (pinfunction "ISEN_4") (pintype "bidirectional"))
    )
    (net (code "63") (name "Net-(U$6-RON{slash}SD)") (class "Default")
      (node (ref "R16") (pin "1") (pinfunction "1_1") (pintype "passive"))
      (node (ref "U$6") (pin "11") (pinfunction "RON/SD_11") (pintype "bidirectional"))
    )
    (net (code "64") (name "Net-(U$6-SS)") (class "Default")
      (node (ref "2.2UF,100V") (pin "1") (pinfunction "1_1") (pintype "passive"))
      (node (ref "U$6") (pin "10") (pinfunction "SS_10") (pintype "bidirectional"))
    )
    (net (code "65") (name "Net-(U$6-SW)") (class "Default")
      (node (ref "0.1UF1") (pin "2") (pinfunction "2_2") (pintype "passive"))
      (node (ref "L1") (pin "1") (pinfunction "1_1") (pintype "passive"))
      (node (ref "U$6") (pin "2") (pinfunction "SW_2") (pintype "bidirectional"))
    )
    (net (code "66") (name "Net-(U$6-VCC)") (class "Default")
      (node (ref "0.1UF2") (pin "1") (pinfunction "1_1") (pintype "passive"))
      (node (ref "U$6") (pin "12") (pinfunction "VCC_12") (pintype "bidirectional"))
    )
    (net (code "67") (name "Net-(U2-ALERT)") (class "Default")
      (node (ref "U$1") (pin "31-CTX3") (pinfunction "31-CTX3_31-CTX3") (pintype "bidirectional"))
      (node (ref "U2") (pin "3") (pinfunction "ALERT_3") (pintype "output"))
    )
    (net (code "68") (name "Net-(U2-IN-)") (class "Default")
      (node (ref "SJ5") (pin "1") (pinfunction "1_1") (pintype "passive"))
      (node (ref "U2") (pin "9") (pinfunction "IN-_9") (pintype "input"))
    )
    (net (code "69") (name "Net-(U2-SCL)") (class "Default")
      (node (ref "R5") (pin "2") (pinfunction "2_2") (pintype "passive"))
      (node (ref "U$1") (pin "19-A5/SCL0") (pinfunction "19-A5/SCL0_19-A5/SCL0") (pintype "bidirectional"))
      (node (ref "U2") (pin "5") (pinfunction "SCL_5") (pintype "input"))
    )
    (net (code "70") (name "Net-(U2-SDA)") (class "Default")
      (node (ref "R2") (pin "2") (pinfunction "2_2") (pintype "passive"))
      (node (ref "U$1") (pin "18-A4/SDA0") (pinfunction "18-A4/SDA0_18-A4/SDA0") (pintype "bidirectional"))
      (node (ref "U2") (pin "4") (pinfunction "SDA_4") (pintype "bidirectional"))
    )
    (net (code "71") (name "Net-(U2-VS)") (class "Default")
      (node (ref "R2") (pin "1") (pinfunction "1_1") (pintype "passive"))
      (node (ref "R5") (pin "1") (pinfunction "1_1") (pintype "passive"))
      (node (ref "R6") (pin "2") (pinfunction "2_2") (pintype "passive"))
      (node (ref "U$1") (pin "3V3-3") (pinfunction "3V3-3_3V3-3") (pintype "bidirectional"))
      (node (ref "U2") (pin "6") (pinfunction "VS_6") (pintype "power_in"))
    )
    (net (code "72") (name "unconnected-(IC2-R2IN-PadP$8)") (class "Default")
      (node (ref "IC2") (pin "P$8") (pinfunction "R2IN_P$8") (pintype "input"))
    )
    (net (code "73") (name "unconnected-(IC2-R2OUT-PadP$9)") (class "Default")
      (node (ref "IC2") (pin "P$9") (pinfunction "R2OUT_P$9") (pintype "output"))
    )
    (net (code "74") (name "unconnected-(IC2-T2IN-PadP$10)") (class "Default")
      (node (ref "IC2") (pin "P$10") (pinfunction "T2IN_P$10") (pintype "input"))
    )
    (net (code "75") (name "unconnected-(IC2-T2OUT-PadP$7)") (class "Default")
      (node (ref "IC2") (pin "P$7") (pinfunction "T2OUT_P$7") (pintype "output"))
    )
    (net (code "76") (name "unconnected-(U$1-5V-Pad+5V)") (class "Default")
      (node (ref "U$1") (pin "+5V") (pinfunction "5V_+5V") (pintype "bidirectional"))
    )
    (net (code "77") (name "unconnected-(U$1-35{slash}TX8-Pad35-TX8)") (class "Default")
      (node (ref "U$1") (pin "35-TX8") (pinfunction "35/TX8_35-TX8") (pintype "bidirectional"))
    )
    (net (code "78") (name "unconnected-(U$1-Pad2-OUT2)") (class "Default")
      (node (ref "U$1") (pin "2-OUT2") (pinfunction "2-OUT2_2-OUT2") (pintype "bidirectional"))
    )
    (net (code "79") (name "unconnected-(U$1-Pad3-LRCLK2)") (class "Default")
      (node (ref "U$1") (pin "3-LRCLK2") (pinfunction "3-LRCLK2_3-LRCLK2") (pintype "bidirectional"))
    )
    (net (code "80") (name "unconnected-(U$1-Pad3V3-1)") (class "Default")
      (node (ref "U$1") (pin "3V3-1") (pinfunction "3V3-1_3V3-1") (pintype "bidirectional"))
    )
    (net (code "81") (name "unconnected-(U$1-Pad3V3-2)") (class "Default")
      (node (ref "U$1") (pin "3V3-2") (pinfunction "3V3-2_3V3-2") (pintype "bidirectional"))
    )
    (net (code "82") (name "unconnected-(U$1-Pad4-BCLK2)") (class "Default")
      (node (ref "U$1") (pin "4-BCLK2") (pinfunction "4-BCLK2_4-BCLK2") (pintype "bidirectional"))
    )
    (net (code "83") (name "unconnected-(U$1-Pad6-OUT1D)") (class "Default")
      (node (ref "U$1") (pin "6-OUT1D") (pinfunction "6-OUT1D_6-OUT1D") (pintype "bidirectional"))
    )
    (net (code "84") (name "unconnected-(U$1-Pad13-SCK{slash}LED)") (class "Default")
      (node (ref "U$1") (pin "13-SCK/LED") (pinfunction "13-SCK/LED_13-SCK/LED") (pintype "bidirectional"))
    )
    (net (code "85") (name "unconnected-(U$1-Pad33-MCLK2)") (class "Default")
      (node (ref "U$1") (pin "33-MCLK2") (pinfunction "33-MCLK2_33-MCLK2") (pintype "bidirectional"))
    )
    (net (code "86") (name "unconnected-(U$1-Pad34-RX8)") (class "Default")
      (node (ref "U$1") (pin "34-RX8") (pinfunction "34-RX8_34-RX8") (pintype "bidirectional"))
    )
    (net (code "87") (name "unconnected-(U$1-Pad36-PWM)") (class "Default")
      (node (ref "U$1") (pin "36-PWM") (pinfunction "36-PWM_36-PWM") (pintype "bidirectional"))
    )
    (net (code "88") (name "unconnected-(U$1-Pad37-PWM)") (class "Default")
      (node (ref "U$1") (pin "37-PWM") (pinfunction "37-PWM_37-PWM") (pintype "bidirectional"))
    )
    (net (code "89") (name "unconnected-(U$1-PadD+)") (class "Default")
      (node (ref "U$1") (pin "D+") (pinfunction "D+_D+") (pintype "bidirectional"))
    )
    (net (code "90") (name "unconnected-(U$1-PadD-)") (class "Default")
      (node (ref "U$1") (pin "D-") (pinfunction "D-_D-") (pintype "bidirectional"))
    )
    (net (code "91") (name "unconnected-(U$1-PadDM)") (class "Default")
      (node (ref "U$1") (pin "DM") (pinfunction "DM_DM") (pintype "bidirectional"))
    )
    (net (code "92") (name "unconnected-(U$1-PadDP)") (class "Default")
      (node (ref "U$1") (pin "DP") (pinfunction "DP_DP") (pintype "bidirectional"))
    )
    (net (code "93") (name "unconnected-(U$1-PadG)") (class "Default")
      (node (ref "U$1") (pin "G") (pinfunction "G_G") (pintype "bidirectional"))
    )
    (net (code "94") (name "unconnected-(U$1-PadLED)") (class "Default")
      (node (ref "U$1") (pin "LED") (pinfunction "LED_LED") (pintype "bidirectional"))
    )
    (net (code "95") (name "unconnected-(U$1-PadON{slash}OFF)") (class "Default")
      (node (ref "U$1") (pin "ON/OFF") (pinfunction "ON/OFF_ON/OFF") (pintype "bidirectional"))
    )
    (net (code "96") (name "unconnected-(U$1-PadPROGRAM)") (class "Default")
      (node (ref "U$1") (pin "PROGRAM") (pinfunction "PROGRAM_PROGRAM") (pintype "bidirectional"))
    )
    (net (code "97") (name "unconnected-(U$1-PadR+)") (class "Default")
      (node (ref "U$1") (pin "R+") (pinfunction "R+_R+") (pintype "bidirectional"))
    )
    (net (code "98") (name "unconnected-(U$1-PadR-)") (class "Default")
      (node (ref "U$1") (pin "R-") (pinfunction "R-_R-") (pintype "bidirectional"))
    )
    (net (code "99") (name "unconnected-(U$1-PadT+)") (class "Default")
      (node (ref "U$1") (pin "T+") (pinfunction "T+_T+") (pintype "bidirectional"))
    )
    (net (code "100") (name "unconnected-(U$1-PadT-)") (class "Default")
      (node (ref "U$1") (pin "T-") (pinfunction "T-_T-") (pintype "bidirectional"))
    )
    (net (code "101") (name "unconnected-(U$1-PadVBAT)") (class "Default")
      (node (ref "U$1") (pin "VBAT") (pinfunction "VBAT_VBAT") (pintype "bidirectional"))
    )
    (net (code "102") (name "unconnected-(U$1-PadVIN)") (class "Default")
      (node (ref "U$1") (pin "VIN") (pinfunction "VIN_VIN") (pintype "bidirectional"))
    )
    (net (code "103") (name "unconnected-(U$1-PadVUSB)") (class "Default")
      (node (ref "U$1") (pin "VUSB") (pinfunction "VUSB_VUSB") (pintype "bidirectional"))
    )
    (net (code "104") (name "unconnected-(U$5-SHTDN-Pad1)") (class "Default")
      (node (ref "U$5") (pin "1") (pinfunction "SHTDN_1") (pintype "bidirectional"))
    )
  )
)
